# SCH_diyson_2024-04-04.net
KiCad netlist of a schematic drawn in EasyEDA
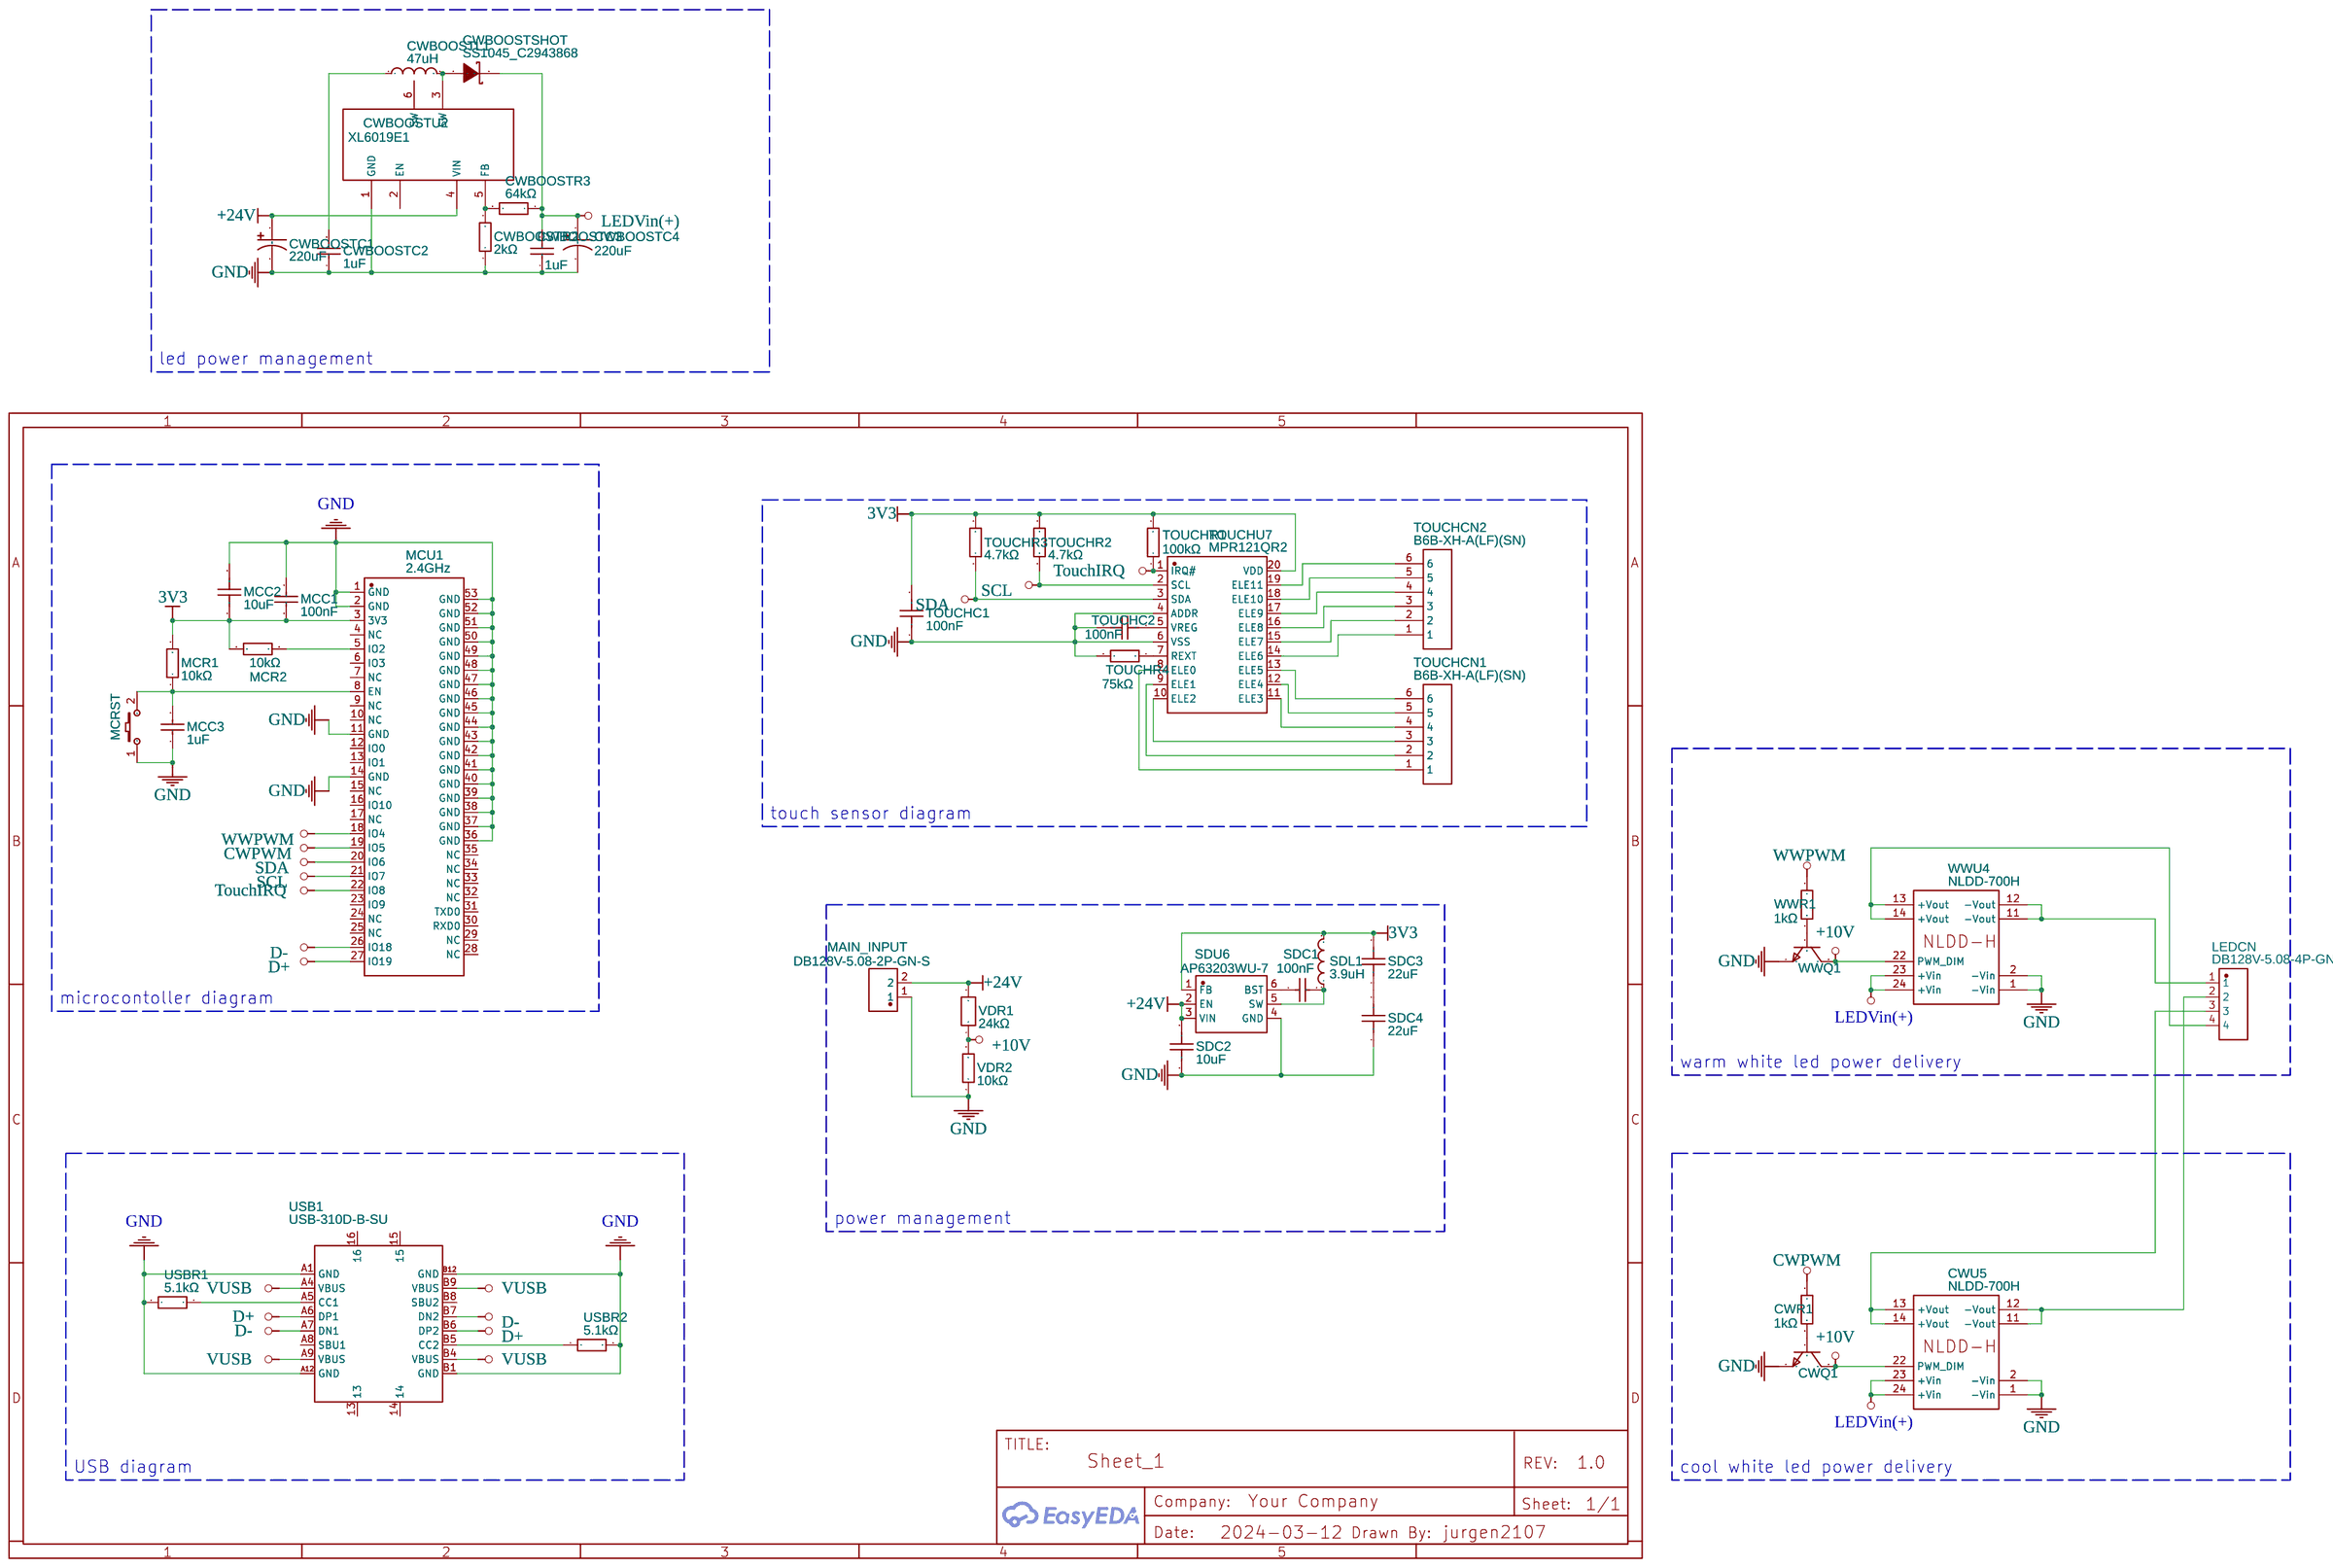
[diagram p0: schematic sheet]

(export (version "E")
  (design (tool "Eeschema 10.0.6"))
  (components
    (comp (ref "CWBOOSTC1")
      (value "220uF")
      (fields
        (field (name "Manufacturer Part") "UUD1V221MNL1GS")
        (field (name "Manufacturer") "Nichicon(尼吉康)")
      )
      (libsource (lib "") (part "UUD1V221MNL1GS"))
    )
    (comp (ref "CWBOOSTC2")
      (value "1uF")
      (fields
        (field (name "Manufacturer Part") "CL10A105KB8NNNC")
        (field (name "Manufacturer") "SAMSUNG(三星)")
      )
      (libsource (lib "") (part "CL10A105KB8NNNC"))
    )
    (comp (ref "CWBOOSTC3")
      (value "1uF")
      (fields
        (field (name "Manufacturer Part") "CL10A105KB8NNNC")
        (field (name "Manufacturer") "SAMSUNG(三星)")
      )
      (libsource (lib "") (part "CL10A105KB8NNNC"))
    )
    (comp (ref "CWBOOSTC4")
      (value "220uF")
      (fields
        (field (name "Manufacturer Part") "UWT1H221MNL1GS")
        (field (name "Manufacturer") "Nichicon(尼吉康)")
      )
      (libsource (lib "") (part "UWT1H221MNL1GS"))
    )
    (comp (ref "CWBOOSTL1")
      (value "47uH")
      (fields (field (name "Manufacturer Part") "MDA1040-470M") (field (name "Manufacturer") "KOHERelec(科或)"))
      (libsource (lib "") (part "MDA1040-470M"))
    )
    (comp (ref "CWBOOSTR2")
      (value "2kΩ")
      (fields
        (field (name "Manufacturer Part") "0603WAF2001T5E")
        (field (name "Manufacturer") "UNI-ROYAL(厚声)")
      )
      (libsource (lib "") (part "0603WAF2001T5E"))
    )
    (comp (ref "CWBOOSTR3")
      (value "64kΩ")
      (fields (field (name "Manufacturer Part") "AR03DTC6402N") (field (name "Manufacturer") "Viking(光颉)"))
      (libsource (lib "") (part "AR03DTC6402N"))
    )
    (comp (ref "CWBOOSTSHOT")
      (value "SS1045_C2943868")
      (fields (field (name "Manufacturer Part") "SS1045") (field (name "Manufacturer") "GOODWORK(固得沃克)"))
      (libsource (lib "") (part "SS1045_C2943868"))
    )
    (comp (ref "CWBOOSTU2")
      (value "XL6019E1")
      (fields (field (name "Manufacturer") "XLSEMI(芯龙)"))
      (libsource (lib "") (part "XL6019E1"))
    )
    (comp (ref "CWQ1")
      (value "2N3904_C2874602")
      (fields (field (name "Manufacturer Part") "2N3904") (field (name "Manufacturer") "JSMSEMI(杰盛微)"))
      (libsource (lib "") (part "2N3904_C2874602_1"))
    )
    (comp (ref "CWR1")
      (value "1kΩ")
      (fields
        (field (name "Manufacturer Part") "0603WAF1001T5E")
        (field (name "Manufacturer") "UNI-ROYAL(厚声)")
      )
      (libsource (lib "") (part "0603WAF1001T5E"))
    )
    (comp (ref "CWU5")
      (value "NLDD-700H")
      (fields (field (name "Manufacturer Part") "709-NLDD-700H") (field (name "Manufacturer") "MEAN WELL"))
      (libsource (lib "") (part "NLDD-700H"))
    )
    (comp (ref "LEDCN")
      (value "DB128V-5.08-4P-GN-S")
      (fields (field (name "Manufacturer") "DORABO(地博电气)"))
      (libsource (lib "") (part "DB128V-5.08-4P-GN-S"))
    )
    (comp (ref "MAIN_INPUT")
      (value "DB128V-5.08-2P-GN-S")
      (fields (field (name "Manufacturer") "DIBO(地博电气)"))
      (libsource (lib "") (part "DB128V-5.08-2P-GN-S"))
    )
    (comp (ref "MCC1")
      (value "100nF")
      (fields
        (field (name "Manufacturer Part") "CL10B104KO8NNNC")
        (field (name "Manufacturer") "SAMSUNG(三星)")
      )
      (libsource (lib "") (part "CL10B104KO8NNNC"))
    )
    (comp (ref "MCC2")
      (value "10uF")
      (fields
        (field (name "Manufacturer Part") "CL10X106MR8NNNC")
        (field (name "Manufacturer") "SAMSUNG(三星)")
      )
      (libsource (lib "") (part "CL10X106MR8NNNC"))
    )
    (comp (ref "MCC3")
      (value "1uF")
      (fields
        (field (name "Manufacturer Part") "CL10A105KP8NNNC")
        (field (name "Manufacturer") "SAMSUNG(三星)")
      )
      (libsource (lib "") (part "CL10A105KP8NNNC"))
    )
    (comp (ref "MCR1")
      (value "10kΩ")
      (fields
        (field (name "Manufacturer Part") "0603WAF1002T5E")
        (field (name "Manufacturer") "UNI-ROYAL(厚声)")
      )
      (libsource (lib "") (part "0603WAF1002T5E_1"))
    )
    (comp (ref "MCR2")
      (value "10kΩ")
      (fields
        (field (name "Manufacturer Part") "0603WAF1002T5E")
        (field (name "Manufacturer") "UNI-ROYAL(厚声)")
      )
      (libsource (lib "") (part "0603WAF1002T5E"))
    )
    (comp (ref "MCRST")
      (value "K2-3.6×6.1_SMD")
      (fields (field (name "Manufacturer Part") "K2-1107ST-A4SW-06"))
      (libsource (lib "") (part "K2-3.6×6.1_SMD"))
    )
    (comp (ref "MCU1")
      (value "2.4GHz")
      (fields
        (field (name "Manufacturer Part") "ESP32-C3-MINI-1-H4")
        (field (name "Manufacturer") "ESPRESSIF(乐鑫)")
      )
      (libsource (lib "") (part "ESP32-C3-MINI-1-H4(4MB)"))
    )
    (comp (ref "SDC1")
      (value "100nF")
      (fields
        (field (name "Manufacturer Part") "CL10B104KA8NNNC")
        (field (name "Manufacturer") "SAMSUNG(三星)")
      )
      (libsource (lib "") (part "CL10B104KA8NNNC"))
    )
    (comp (ref "SDC2")
      (value "10uF")
      (fields
        (field (name "Manufacturer Part") "CL10A106MA8NRNC")
        (field (name "Manufacturer") "SAMSUNG(三星)")
      )
      (libsource (lib "") (part "CL10A106MA8NRNC"))
    )
    (comp (ref "SDC3")
      (value "22uF")
      (fields
        (field (name "Manufacturer Part") "CL10A226MP8NUNE")
        (field (name "Manufacturer") "SAMSUNG(三星)")
      )
      (libsource (lib "") (part "CL10A226MP8NUNE"))
    )
    (comp (ref "SDC4")
      (value "22uF")
      (fields
        (field (name "Manufacturer Part") "CL10A226MP8NUNE")
        (field (name "Manufacturer") "SAMSUNG(三星)")
      )
      (libsource (lib "") (part "CL10A226MP8NUNE"))
    )
    (comp (ref "SDL1")
      (value "3.9uH")
      (fields (field (name "Manufacturer Part") "FHW1812IF3R9JST") (field (name "Manufacturer") "FH(风华)"))
      (libsource (lib "") (part "FHW1812IF3R9JST"))
    )
    (comp (ref "SDU6")
      (value "AP63203WU-7")
      (fields (field (name "Manufacturer") "DIODES(美台)"))
      (libsource (lib "") (part "AP63203WU-7"))
    )
    (comp (ref "TOUCHC1")
      (value "100nF")
      (fields
        (field (name "Manufacturer Part") "CL10B104KB8NNNC")
        (field (name "Manufacturer") "SAMSUNG(三星)")
      )
      (libsource (lib "") (part "CL10B104KB8NNNC_1"))
    )
    (comp (ref "TOUCHC2")
      (value "100nF")
      (fields
        (field (name "Manufacturer Part") "CL10B104KB8NNNC")
        (field (name "Manufacturer") "SAMSUNG(三星)")
      )
      (libsource (lib "") (part "CL10B104KB8NNNC"))
    )
    (comp (ref "TOUCHCN1")
      (value "B6B-XH-A(LF)(SN)")
      (fields (field (name "Manufacturer") "JST"))
      (libsource (lib "") (part "B6B-XH-A(LF)(SN)"))
    )
    (comp (ref "TOUCHCN2")
      (value "B6B-XH-A(LF)(SN)")
      (fields (field (name "Manufacturer") "JST"))
      (libsource (lib "") (part "B6B-XH-A(LF)(SN)"))
    )
    (comp (ref "TOUCHR1")
      (value "100kΩ")
      (fields
        (field (name "Manufacturer Part") "0603WAF1003T5E")
        (field (name "Manufacturer") "UNI-ROYAL(厚声)")
      )
      (libsource (lib "") (part "0603WAF1003T5E"))
    )
    (comp (ref "TOUCHR2")
      (value "4.7kΩ")
      (fields
        (field (name "Manufacturer Part") "0603WAF4701T5E")
        (field (name "Manufacturer") "UNI-ROYAL(厚声)")
      )
      (libsource (lib "") (part "0603WAF4701T5E"))
    )
    (comp (ref "TOUCHR3")
      (value "4.7kΩ")
      (fields
        (field (name "Manufacturer Part") "0603WAF4701T5E")
        (field (name "Manufacturer") "UNI-ROYAL(厚声)")
      )
      (libsource (lib "") (part "0603WAF4701T5E"))
    )
    (comp (ref "TOUCHR4")
      (value "75kΩ")
      (fields
        (field (name "Manufacturer Part") "0603WAF7502T5E")
        (field (name "Manufacturer") "UNI-ROYAL(厚声)")
      )
      (libsource (lib "") (part "0603WAF7502T5E"))
    )
    (comp (ref "TOUCHU7")
      (value "MPR121QR2")
      (fields (field (name "Manufacturer") "NXP(恩智浦)"))
      (libsource (lib "") (part "MPR121QR2"))
    )
    (comp (ref "USB1")
      (value "USB-310D-B-SU")
      (fields (field (name "Manufacturer") "HOOYA(皓宇电子)"))
      (libsource (lib "") (part "USB-310D-B-SU"))
    )
    (comp (ref "USBR1")
      (value "5.1kΩ")
      (fields
        (field (name "Manufacturer Part") "0603WAF5101T5E")
        (field (name "Manufacturer") "UNI-ROYAL(厚声)")
      )
      (libsource (lib "") (part "0603WAF5101T5E"))
    )
    (comp (ref "USBR2")
      (value "5.1kΩ")
      (fields
        (field (name "Manufacturer Part") "0603WAF5101T5E")
        (field (name "Manufacturer") "UNI-ROYAL(厚声)")
      )
      (libsource (lib "") (part "0603WAF5101T5E"))
    )
    (comp (ref "VDR1")
      (value "24kΩ")
      (fields (field (name "Manufacturer Part") "ERJPB3B2402V") (field (name "Manufacturer") "PANASONIC(松下)"))
      (libsource (lib "") (part "ERJPB3B2402V"))
    )
    (comp (ref "VDR2")
      (value "10kΩ")
      (fields (field (name "Manufacturer Part") "ERJPB3B1002V") (field (name "Manufacturer") "PANASONIC(松下)"))
      (libsource (lib "") (part "ERJPB3B1002V"))
    )
    (comp (ref "WWQ1")
      (value "2N3904_C2874602")
      (fields (field (name "Manufacturer Part") "2N3904") (field (name "Manufacturer") "JSMSEMI(杰盛微)"))
      (libsource (lib "") (part "2N3904_C2874602"))
    )
    (comp (ref "WWR1")
      (value "1kΩ")
      (fields
        (field (name "Manufacturer Part") "0603WAF1001T5E")
        (field (name "Manufacturer") "UNI-ROYAL(厚声)")
      )
      (libsource (lib "") (part "0603WAF1001T5E_1"))
    )
    (comp (ref "WWU4")
      (value "NLDD-700H")
      (fields (field (name "Manufacturer Part") "709-NLDD-700H") (field (name "Manufacturer") "MEAN WELL"))
      (libsource (lib "") (part "NLDD-700H_1"))
    )
  )
  (nets
    (net (code "1") (name "+10V") (class "Default")
      (node (ref "CWQ1") (pin "3") (pinfunction "C_3") (pintype "unspecified"))
      (node (ref "CWU5") (pin "22") (pinfunction "PWM_DIM_22") (pintype "unspecified"))
      (node (ref "VDR1") (pin "1") (pinfunction "1_1") (pintype "unspecified"))
      (node (ref "VDR2") (pin "2") (pinfunction "2_2") (pintype "unspecified"))
      (node (ref "WWQ1") (pin "3") (pinfunction "C_3") (pintype "unspecified"))
      (node (ref "WWU4") (pin "22") (pinfunction "PWM_DIM_22") (pintype "unspecified"))
    )
    (net (code "2") (name "+24V") (class "Default")
      (node (ref "CWBOOSTC1") (pin "1") (pinfunction "1_1") (pintype "unspecified"))
      (node (ref "CWBOOSTU2") (pin "4") (pinfunction "VIN_4") (pintype "unspecified"))
      (node (ref "MAIN_INPUT") (pin "2") (pinfunction "2_2") (pintype "unspecified"))
      (node (ref "SDC2") (pin "2") (pinfunction "2_2") (pintype "unspecified"))
      (node (ref "SDU6") (pin "2") (pinfunction "EN_2") (pintype "unspecified"))
      (node (ref "SDU6") (pin "3") (pinfunction "VIN_3") (pintype "unspecified"))
      (node (ref "VDR1") (pin "2") (pinfunction "2_2") (pintype "unspecified"))
    )
    (net (code "3") (name "3V3") (class "Default")
      (node (ref "MCC1") (pin "1") (pinfunction "1_1") (pintype "input"))
      (node (ref "MCC2") (pin "1") (pinfunction "1_1") (pintype "unspecified"))
      (node (ref "MCR1") (pin "2") (pinfunction "2_2") (pintype "input"))
      (node (ref "MCR2") (pin "2") (pinfunction "2_2") (pintype "input"))
      (node (ref "MCU1") (pin "3") (pinfunction "3V3_3") (pintype "unspecified"))
      (node (ref "SDC3") (pin "2") (pinfunction "2_2") (pintype "unspecified"))
      (node (ref "SDL1") (pin "2") (pinfunction "2_2") (pintype "unspecified"))
      (node (ref "SDU6") (pin "1") (pinfunction "FB_1") (pintype "unspecified"))
      (node (ref "TOUCHC1") (pin "2") (pinfunction "2_2") (pintype "unspecified"))
      (node (ref "TOUCHR1") (pin "2") (pinfunction "2_2") (pintype "input"))
      (node (ref "TOUCHR2") (pin "2") (pinfunction "2_2") (pintype "input"))
      (node (ref "TOUCHR3") (pin "2") (pinfunction "2_2") (pintype "input"))
      (node (ref "TOUCHU7") (pin "20") (pinfunction "VDD_20") (pintype "unspecified"))
    )
    (net (code "4") (name "CWPWM") (class "Default")
      (node (ref "CWR1") (pin "1") (pinfunction "1_1") (pintype "input"))
      (node (ref "MCU1") (pin "19") (pinfunction "IO5_19") (pintype "unspecified"))
    )
    (net (code "5") (name "D+") (class "Default")
      (node (ref "MCU1") (pin "27") (pinfunction "IO19_27") (pintype "unspecified"))
      (node (ref "USB1") (pin "A6") (pinfunction "DP1_A6") (pintype "unspecified"))
      (node (ref "USB1") (pin "B6") (pinfunction "DP2_B6") (pintype "unspecified"))
    )
    (net (code "6") (name "D-") (class "Default")
      (node (ref "MCU1") (pin "26") (pinfunction "IO18_26") (pintype "unspecified"))
      (node (ref "USB1") (pin "A7") (pinfunction "DN1_A7") (pintype "unspecified"))
      (node (ref "USB1") (pin "B7") (pinfunction "DN2_B7") (pintype "unspecified"))
    )
    (net (code "7") (name "GND") (class "Default")
      (node (ref "CWBOOSTC1") (pin "2") (pinfunction "2_2") (pintype "unspecified"))
      (node (ref "CWBOOSTC2") (pin "1") (pinfunction "1_1") (pintype "input"))
      (node (ref "CWBOOSTC3") (pin "1") (pinfunction "1_1") (pintype "input"))
      (node (ref "CWBOOSTC4") (pin "2") (pinfunction "2_2") (pintype "unspecified"))
      (node (ref "CWBOOSTR2") (pin "1") (pinfunction "1_1") (pintype "input"))
      (node (ref "CWBOOSTU2") (pin "1") (pinfunction "GND_1") (pintype "unspecified"))
      (node (ref "CWQ1") (pin "1") (pinfunction "E_1") (pintype "unspecified"))
      (node (ref "CWU5") (pin "1") (pinfunction "-Vin_1") (pintype "unspecified"))
      (node (ref "CWU5") (pin "2") (pinfunction "-Vin_2") (pintype "unspecified"))
      (node (ref "MAIN_INPUT") (pin "1") (pinfunction "1_1") (pintype "unspecified"))
      (node (ref "MCC1") (pin "2") (pinfunction "2_2") (pintype "input"))
      (node (ref "MCC2") (pin "2") (pinfunction "2_2") (pintype "unspecified"))
      (node (ref "MCC3") (pin "1") (pinfunction "1_1") (pintype "input"))
      (node (ref "MCRST") (pin "1") (pinfunction "1_1") (pintype "unspecified"))
      (node (ref "MCU1") (pin "1") (pinfunction "GND_1") (pintype "unspecified"))
      (node (ref "MCU1") (pin "11") (pinfunction "GND_11") (pintype "unspecified"))
      (node (ref "MCU1") (pin "14") (pinfunction "GND_14") (pintype "unspecified"))
      (node (ref "MCU1") (pin "2") (pinfunction "GND_2") (pintype "unspecified"))
      (node (ref "MCU1") (pin "36") (pinfunction "GND_36") (pintype "unspecified"))
      (node (ref "MCU1") (pin "37") (pinfunction "GND_37") (pintype "unspecified"))
      (node (ref "MCU1") (pin "38") (pinfunction "GND_38") (pintype "unspecified"))
      (node (ref "MCU1") (pin "39") (pinfunction "GND_39") (pintype "unspecified"))
      (node (ref "MCU1") (pin "40") (pinfunction "GND_40") (pintype "unspecified"))
      (node (ref "MCU1") (pin "41") (pinfunction "GND_41") (pintype "unspecified"))
      (node (ref "MCU1") (pin "42") (pinfunction "GND_42") (pintype "unspecified"))
      (node (ref "MCU1") (pin "43") (pinfunction "GND_43") (pintype "unspecified"))
      (node (ref "MCU1") (pin "44") (pinfunction "GND_44") (pintype "unspecified"))
      (node (ref "MCU1") (pin "45") (pinfunction "GND_45") (pintype "unspecified"))
      (node (ref "MCU1") (pin "46") (pinfunction "GND_46") (pintype "unspecified"))
      (node (ref "MCU1") (pin "47") (pinfunction "GND_47") (pintype "unspecified"))
      (node (ref "MCU1") (pin "48") (pinfunction "GND_48") (pintype "unspecified"))
      (node (ref "MCU1") (pin "49") (pinfunction "GND_49") (pintype "unspecified"))
      (node (ref "MCU1") (pin "50") (pinfunction "GND_50") (pintype "unspecified"))
      (node (ref "MCU1") (pin "51") (pinfunction "GND_51") (pintype "unspecified"))
      (node (ref "MCU1") (pin "52") (pinfunction "GND_52") (pintype "unspecified"))
      (node (ref "MCU1") (pin "53") (pinfunction "GND_53") (pintype "unspecified"))
      (node (ref "SDC2") (pin "1") (pinfunction "1_1") (pintype "unspecified"))
      (node (ref "SDC4") (pin "1") (pinfunction "1_1") (pintype "unspecified"))
      (node (ref "SDU6") (pin "4") (pinfunction "GND_4") (pintype "unspecified"))
      (node (ref "TOUCHC1") (pin "1") (pinfunction "1_1") (pintype "unspecified"))
      (node (ref "TOUCHC2") (pin "1") (pinfunction "1_1") (pintype "unspecified"))
      (node (ref "TOUCHR4") (pin "2") (pinfunction "2_2") (pintype "input"))
      (node (ref "TOUCHU7") (pin "4") (pinfunction "ADDR_4") (pintype "unspecified"))
      (node (ref "TOUCHU7") (pin "6") (pinfunction "VSS_6") (pintype "unspecified"))
      (node (ref "USB1") (pin "A1") (pinfunction "GND_A1") (pintype "unspecified"))
      (node (ref "USB1") (pin "A12") (pinfunction "GND_A12") (pintype "unspecified"))
      (node (ref "USB1") (pin "B1") (pinfunction "GND_B1") (pintype "unspecified"))
      (node (ref "USB1") (pin "B12") (pinfunction "GND_B12") (pintype "unspecified"))
      (node (ref "USBR1") (pin "1") (pinfunction "1_1") (pintype "input"))
      (node (ref "USBR2") (pin "2") (pinfunction "2_2") (pintype "input"))
      (node (ref "VDR2") (pin "1") (pinfunction "1_1") (pintype "unspecified"))
      (node (ref "WWQ1") (pin "1") (pinfunction "E_1") (pintype "unspecified"))
      (node (ref "WWU4") (pin "1") (pinfunction "-Vin_1") (pintype "unspecified"))
      (node (ref "WWU4") (pin "2") (pinfunction "-Vin_2") (pintype "unspecified"))
    )
    (net (code "8") (name "LEDVin(+)") (class "Default")
      (node (ref "CWBOOSTC3") (pin "2") (pinfunction "2_2") (pintype "input"))
      (node (ref "CWBOOSTC4") (pin "1") (pinfunction "1_1") (pintype "unspecified"))
      (node (ref "CWBOOSTR3") (pin "1") (pinfunction "1_1") (pintype "unspecified"))
      (node (ref "CWBOOSTSHOT") (pin "1") (pinfunction "C_1") (pintype "unspecified"))
      (node (ref "CWU5") (pin "23") (pinfunction "+Vin_23") (pintype "unspecified"))
      (node (ref "CWU5") (pin "24") (pinfunction "+Vin_24") (pintype "unspecified"))
      (node (ref "WWU4") (pin "23") (pinfunction "+Vin_23") (pintype "unspecified"))
      (node (ref "WWU4") (pin "24") (pinfunction "+Vin_24") (pintype "unspecified"))
    )
    (net (code "9") (name "Net-(CWBOOSTC2-Pad2)") (class "Default")
      (node (ref "CWBOOSTC2") (pin "2") (pinfunction "2_2") (pintype "input"))
      (node (ref "CWBOOSTL1") (pin "1") (pinfunction "1_1") (pintype "unspecified"))
    )
    (net (code "10") (name "Net-(CWBOOSTSHOT-A)") (class "Default")
      (node (ref "CWBOOSTL1") (pin "2") (pinfunction "2_2") (pintype "unspecified"))
      (node (ref "CWBOOSTSHOT") (pin "2") (pinfunction "A_2") (pintype "unspecified"))
      (node (ref "CWBOOSTU2") (pin "3") (pinfunction "SW_3") (pintype "unspecified"))
    )
    (net (code "11") (name "Net-(CWBOOSTU2-FB)") (class "Default")
      (node (ref "CWBOOSTR2") (pin "2") (pinfunction "2_2") (pintype "input"))
      (node (ref "CWBOOSTR3") (pin "2") (pinfunction "2_2") (pintype "unspecified"))
      (node (ref "CWBOOSTU2") (pin "5") (pinfunction "FB_5") (pintype "unspecified"))
    )
    (net (code "12") (name "Net-(CWQ1-B)") (class "Default")
      (node (ref "CWQ1") (pin "2") (pinfunction "B_2") (pintype "unspecified"))
      (node (ref "CWR1") (pin "2") (pinfunction "2_2") (pintype "input"))
    )
    (net (code "13") (name "Net-(CWU5-+Vout-Pad13)") (class "Default")
      (node (ref "CWU5") (pin "13") (pinfunction "+Vout_13") (pintype "unspecified"))
      (node (ref "CWU5") (pin "14") (pinfunction "+Vout_14") (pintype "unspecified"))
      (node (ref "LEDCN") (pin "3") (pinfunction "3_3") (pintype "unspecified"))
    )
    (net (code "14") (name "Net-(CWU5--Vout-Pad11)") (class "Default")
      (node (ref "CWU5") (pin "11") (pinfunction "-Vout_11") (pintype "unspecified"))
      (node (ref "CWU5") (pin "12") (pinfunction "-Vout_12") (pintype "unspecified"))
      (node (ref "LEDCN") (pin "2") (pinfunction "2_2") (pintype "unspecified"))
    )
    (net (code "15") (name "Net-(LEDCN-Pad1)") (class "Default")
      (node (ref "LEDCN") (pin "1") (pinfunction "1_1") (pintype "unspecified"))
      (node (ref "WWU4") (pin "11") (pinfunction "-Vout_11") (pintype "unspecified"))
      (node (ref "WWU4") (pin "12") (pinfunction "-Vout_12") (pintype "unspecified"))
    )
    (net (code "16") (name "Net-(LEDCN-Pad4)") (class "Default")
      (node (ref "LEDCN") (pin "4") (pinfunction "4_4") (pintype "unspecified"))
      (node (ref "WWU4") (pin "13") (pinfunction "+Vout_13") (pintype "unspecified"))
      (node (ref "WWU4") (pin "14") (pinfunction "+Vout_14") (pintype "unspecified"))
    )
    (net (code "17") (name "Net-(MCU1-EN)") (class "Default")
      (node (ref "MCC3") (pin "2") (pinfunction "2_2") (pintype "input"))
      (node (ref "MCR1") (pin "1") (pinfunction "1_1") (pintype "input"))
      (node (ref "MCRST") (pin "2") (pinfunction "2_2") (pintype "unspecified"))
      (node (ref "MCU1") (pin "8") (pinfunction "EN_8") (pintype "unspecified"))
    )
    (net (code "18") (name "Net-(MCU1-IO2)") (class "Default")
      (node (ref "MCR2") (pin "1") (pinfunction "1_1") (pintype "input"))
      (node (ref "MCU1") (pin "5") (pinfunction "IO2_5") (pintype "unspecified"))
    )
    (net (code "19") (name "Net-(SDC3-Pad1)") (class "Default")
      (node (ref "SDC3") (pin "1") (pinfunction "1_1") (pintype "unspecified"))
      (node (ref "SDC4") (pin "2") (pinfunction "2_2") (pintype "unspecified"))
    )
    (net (code "20") (name "Net-(SDU6-BST)") (class "Default")
      (node (ref "SDC1") (pin "1") (pinfunction "1_1") (pintype "input"))
      (node (ref "SDU6") (pin "6") (pinfunction "BST_6") (pintype "unspecified"))
    )
    (net (code "21") (name "Net-(SDU6-SW)") (class "Default")
      (node (ref "SDC1") (pin "2") (pinfunction "2_2") (pintype "input"))
      (node (ref "SDL1") (pin "1") (pinfunction "1_1") (pintype "unspecified"))
      (node (ref "SDU6") (pin "5") (pinfunction "SW_5") (pintype "unspecified"))
    )
    (net (code "22") (name "Net-(TOUCHU7-ELE0)") (class "Default")
      (node (ref "TOUCHCN1") (pin "1") (pinfunction "1_1") (pintype "unspecified"))
      (node (ref "TOUCHU7") (pin "8") (pinfunction "ELE0_8") (pintype "unspecified"))
    )
    (net (code "23") (name "Net-(TOUCHU7-ELE1)") (class "Default")
      (node (ref "TOUCHCN1") (pin "2") (pinfunction "2_2") (pintype "unspecified"))
      (node (ref "TOUCHU7") (pin "9") (pinfunction "ELE1_9") (pintype "unspecified"))
    )
    (net (code "24") (name "Net-(TOUCHU7-ELE2)") (class "Default")
      (node (ref "TOUCHCN1") (pin "3") (pinfunction "3_3") (pintype "unspecified"))
      (node (ref "TOUCHU7") (pin "10") (pinfunction "ELE2_10") (pintype "unspecified"))
    )
    (net (code "25") (name "Net-(TOUCHU7-ELE3)") (class "Default")
      (node (ref "TOUCHCN1") (pin "4") (pinfunction "4_4") (pintype "unspecified"))
      (node (ref "TOUCHU7") (pin "11") (pinfunction "ELE3_11") (pintype "unspecified"))
    )
    (net (code "26") (name "Net-(TOUCHU7-ELE4)") (class "Default")
      (node (ref "TOUCHCN1") (pin "5") (pinfunction "5_5") (pintype "unspecified"))
      (node (ref "TOUCHU7") (pin "12") (pinfunction "ELE4_12") (pintype "unspecified"))
    )
    (net (code "27") (name "Net-(TOUCHU7-ELE5)") (class "Default")
      (node (ref "TOUCHCN1") (pin "6") (pinfunction "6_6") (pintype "unspecified"))
      (node (ref "TOUCHU7") (pin "13") (pinfunction "ELE5_13") (pintype "unspecified"))
    )
    (net (code "28") (name "Net-(TOUCHU7-ELE6)") (class "Default")
      (node (ref "TOUCHCN2") (pin "1") (pinfunction "1_1") (pintype "unspecified"))
      (node (ref "TOUCHU7") (pin "14") (pinfunction "ELE6_14") (pintype "unspecified"))
    )
    (net (code "29") (name "Net-(TOUCHU7-ELE7)") (class "Default")
      (node (ref "TOUCHCN2") (pin "2") (pinfunction "2_2") (pintype "unspecified"))
      (node (ref "TOUCHU7") (pin "15") (pinfunction "ELE7_15") (pintype "unspecified"))
    )
    (net (code "30") (name "Net-(TOUCHU7-ELE8)") (class "Default")
      (node (ref "TOUCHCN2") (pin "3") (pinfunction "3_3") (pintype "unspecified"))
      (node (ref "TOUCHU7") (pin "16") (pinfunction "ELE8_16") (pintype "unspecified"))
    )
    (net (code "31") (name "Net-(TOUCHU7-ELE9)") (class "Default")
      (node (ref "TOUCHCN2") (pin "4") (pinfunction "4_4") (pintype "unspecified"))
      (node (ref "TOUCHU7") (pin "17") (pinfunction "ELE9_17") (pintype "unspecified"))
    )
    (net (code "32") (name "Net-(TOUCHU7-ELE10)") (class "Default")
      (node (ref "TOUCHCN2") (pin "5") (pinfunction "5_5") (pintype "unspecified"))
      (node (ref "TOUCHU7") (pin "18") (pinfunction "ELE10_18") (pintype "unspecified"))
    )
    (net (code "33") (name "Net-(TOUCHU7-ELE11)") (class "Default")
      (node (ref "TOUCHCN2") (pin "6") (pinfunction "6_6") (pintype "unspecified"))
      (node (ref "TOUCHU7") (pin "19") (pinfunction "ELE11_19") (pintype "unspecified"))
    )
    (net (code "34") (name "Net-(TOUCHU7-REXT)") (class "Default")
      (node (ref "TOUCHR4") (pin "1") (pinfunction "1_1") (pintype "input"))
      (node (ref "TOUCHU7") (pin "7") (pinfunction "REXT_7") (pintype "unspecified"))
    )
    (net (code "35") (name "Net-(TOUCHU7-VREG)") (class "Default")
      (node (ref "TOUCHC2") (pin "2") (pinfunction "2_2") (pintype "unspecified"))
      (node (ref "TOUCHU7") (pin "5") (pinfunction "VREG_5") (pintype "unspecified"))
    )
    (net (code "36") (name "Net-(USB1-CC1)") (class "Default")
      (node (ref "USB1") (pin "A5") (pinfunction "CC1_A5") (pintype "unspecified"))
      (node (ref "USBR1") (pin "2") (pinfunction "2_2") (pintype "input"))
    )
    (net (code "37") (name "Net-(USB1-CC2)") (class "Default")
      (node (ref "USB1") (pin "B5") (pinfunction "CC2_B5") (pintype "unspecified"))
      (node (ref "USBR2") (pin "1") (pinfunction "1_1") (pintype "input"))
    )
    (net (code "38") (name "Net-(WWQ1-B)") (class "Default")
      (node (ref "WWQ1") (pin "2") (pinfunction "B_2") (pintype "unspecified"))
      (node (ref "WWR1") (pin "2") (pinfunction "2_2") (pintype "input"))
    )
    (net (code "39") (name "SCL") (class "Default")
      (node (ref "MCU1") (pin "21") (pinfunction "IO7_21") (pintype "unspecified"))
      (node (ref "TOUCHR2") (pin "1") (pinfunction "1_1") (pintype "input"))
      (node (ref "TOUCHU7") (pin "2") (pinfunction "SCL_2") (pintype "unspecified"))
    )
    (net (code "40") (name "SDA") (class "Default")
      (node (ref "MCU1") (pin "20") (pinfunction "IO6_20") (pintype "unspecified"))
      (node (ref "TOUCHR3") (pin "1") (pinfunction "1_1") (pintype "input"))
      (node (ref "TOUCHU7") (pin "3") (pinfunction "SDA_3") (pintype "unspecified"))
    )
    (net (code "41") (name "TouchIRQ") (class "Default")
      (node (ref "MCU1") (pin "22") (pinfunction "IO8_22") (pintype "unspecified"))
      (node (ref "TOUCHR1") (pin "1") (pinfunction "1_1") (pintype "input"))
      (node (ref "TOUCHU7") (pin "1") (pinfunction "IRQ#_1") (pintype "unspecified"))
    )
    (net (code "42") (name "VUSB") (class "Default")
      (node (ref "USB1") (pin "A4") (pinfunction "VBUS_A4") (pintype "unspecified"))
      (node (ref "USB1") (pin "A9") (pinfunction "VBUS_A9") (pintype "unspecified"))
      (node (ref "USB1") (pin "B4") (pinfunction "VBUS_B4") (pintype "unspecified"))
      (node (ref "USB1") (pin "B9") (pinfunction "VBUS_B9") (pintype "unspecified"))
    )
    (net (code "43") (name "WWPWM") (class "Default")
      (node (ref "MCU1") (pin "18") (pinfunction "IO4_18") (pintype "unspecified"))
      (node (ref "WWR1") (pin "1") (pinfunction "1_1") (pintype "input"))
    )
    (net (code "44") (name "unconnected-(CWBOOSTU2-EN-Pad2)") (class "Default")
      (node (ref "CWBOOSTU2") (pin "2") (pinfunction "EN_2") (pintype "unspecified"))
    )
    (net (code "45") (name "unconnected-(CWBOOSTU2-SW-Pad6)") (class "Default")
      (node (ref "CWBOOSTU2") (pin "6") (pinfunction "SW_6") (pintype "unspecified"))
    )
    (net (code "46") (name "unconnected-(MCU1-IO0-Pad12)") (class "Default")
      (node (ref "MCU1") (pin "12") (pinfunction "IO0_12") (pintype "unspecified"))
    )
    (net (code "47") (name "unconnected-(MCU1-IO1-Pad13)") (class "Default")
      (node (ref "MCU1") (pin "13") (pinfunction "IO1_13") (pintype "unspecified"))
    )
    (net (code "48") (name "unconnected-(MCU1-IO3-Pad6)") (class "Default")
      (node (ref "MCU1") (pin "6") (pinfunction "IO3_6") (pintype "unspecified"))
    )
    (net (code "49") (name "unconnected-(MCU1-IO9-Pad23)") (class "Default")
      (node (ref "MCU1") (pin "23") (pinfunction "IO9_23") (pintype "unspecified"))
    )
    (net (code "50") (name "unconnected-(MCU1-IO10-Pad16)") (class "Default")
      (node (ref "MCU1") (pin "16") (pinfunction "IO10_16") (pintype "unspecified"))
    )
    (net (code "51") (name "unconnected-(MCU1-NC-Pad4)") (class "Default")
      (node (ref "MCU1") (pin "4") (pinfunction "NC_4") (pintype "unspecified"))
    )
    (net (code "52") (name "unconnected-(MCU1-NC-Pad7)") (class "Default")
      (node (ref "MCU1") (pin "7") (pinfunction "NC_7") (pintype "unspecified"))
    )
    (net (code "53") (name "unconnected-(MCU1-NC-Pad9)") (class "Default")
      (node (ref "MCU1") (pin "9") (pinfunction "NC_9") (pintype "unspecified"))
    )
    (net (code "54") (name "unconnected-(MCU1-NC-Pad10)") (class "Default")
      (node (ref "MCU1") (pin "10") (pinfunction "NC_10") (pintype "unspecified"))
    )
    (net (code "55") (name "unconnected-(MCU1-NC-Pad15)") (class "Default")
      (node (ref "MCU1") (pin "15") (pinfunction "NC_15") (pintype "unspecified"))
    )
    (net (code "56") (name "unconnected-(MCU1-NC-Pad17)") (class "Default")
      (node (ref "MCU1") (pin "17") (pinfunction "NC_17") (pintype "unspecified"))
    )
    (net (code "57") (name "unconnected-(MCU1-NC-Pad24)") (class "Default")
      (node (ref "MCU1") (pin "24") (pinfunction "NC_24") (pintype "unspecified"))
    )
    (net (code "58") (name "unconnected-(MCU1-NC-Pad25)") (class "Default")
      (node (ref "MCU1") (pin "25") (pinfunction "NC_25") (pintype "unspecified"))
    )
    (net (code "59") (name "unconnected-(MCU1-NC-Pad28)") (class "Default")
      (node (ref "MCU1") (pin "28") (pinfunction "NC_28") (pintype "unspecified"))
    )
    (net (code "60") (name "unconnected-(MCU1-NC-Pad29)") (class "Default")
      (node (ref "MCU1") (pin "29") (pinfunction "NC_29") (pintype "unspecified"))
    )
    (net (code "61") (name "unconnected-(MCU1-NC-Pad32)") (class "Default")
      (node (ref "MCU1") (pin "32") (pinfunction "NC_32") (pintype "unspecified"))
    )
    (net (code "62") (name "unconnected-(MCU1-NC-Pad33)") (class "Default")
      (node (ref "MCU1") (pin "33") (pinfunction "NC_33") (pintype "unspecified"))
    )
    (net (code "63") (name "unconnected-(MCU1-NC-Pad34)") (class "Default")
      (node (ref "MCU1") (pin "34") (pinfunction "NC_34") (pintype "unspecified"))
    )
    (net (code "64") (name "unconnected-(MCU1-NC-Pad35)") (class "Default")
      (node (ref "MCU1") (pin "35") (pinfunction "NC_35") (pintype "unspecified"))
    )
    (net (code "65") (name "unconnected-(MCU1-RXD0-Pad30)") (class "Default")
      (node (ref "MCU1") (pin "30") (pinfunction "RXD0_30") (pintype "unspecified"))
    )
    (net (code "66") (name "unconnected-(MCU1-TXD0-Pad31)") (class "Default")
      (node (ref "MCU1") (pin "31") (pinfunction "TXD0_31") (pintype "unspecified"))
    )
    (net (code "67") (name "unconnected-(USB1-Pad13)") (class "Default")
      (node (ref "USB1") (pin "13") (pinfunction "13_13") (pintype "unspecified"))
    )
    (net (code "68") (name "unconnected-(USB1-Pad14)") (class "Default")
      (node (ref "USB1") (pin "14") (pinfunction "14_14") (pintype "unspecified"))
    )
    (net (code "69") (name "unconnected-(USB1-Pad15)") (class "Default")
      (node (ref "USB1") (pin "15") (pinfunction "15_15") (pintype "unspecified"))
    )
    (net (code "70") (name "unconnected-(USB1-Pad16)") (class "Default")
      (node (ref "USB1") (pin "16") (pinfunction "16_16") (pintype "unspecified"))
    )
    (net (code "71") (name "unconnected-(USB1-SBU1-PadA8)") (class "Default")
      (node (ref "USB1") (pin "A8") (pinfunction "SBU1_A8") (pintype "unspecified"))
    )
    (net (code "72") (name "unconnected-(USB1-SBU2-PadB8)") (class "Default")
      (node (ref "USB1") (pin "B8") (pinfunction "SBU2_B8") (pintype "unspecified"))
    )
  )
)
